# StepperDriver_Rev1.net
KiCad netlist of a schematic drawn in EAGLE
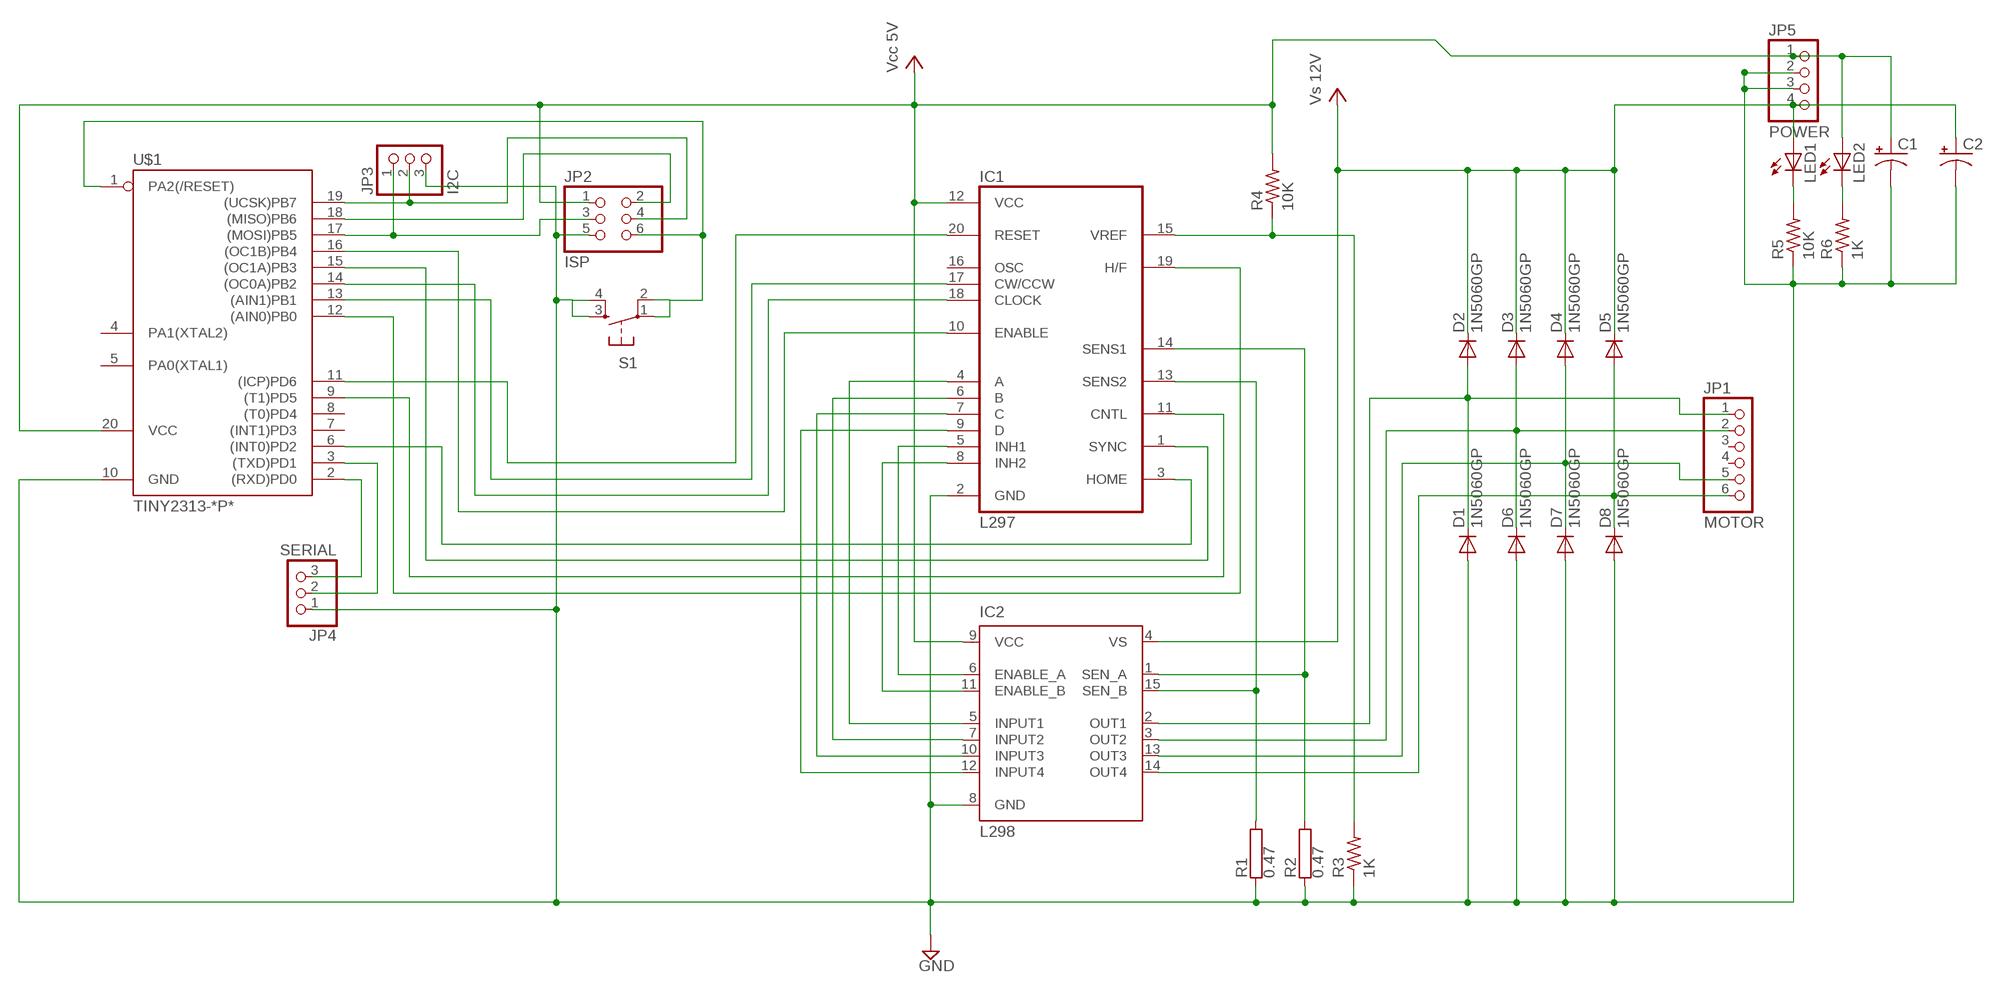
[diagram p0: schematic, sheet 1]

(export (version "E")
  (design (tool "Eeschema 10.0.6"))
  (components
    (comp (ref "C1")
      (value "CPOL-USE2.5-6")
      (footprint "eagle-import:E2,5-6")
      (libsource (lib "eagle-import") (part "CPOL-USE2.5-6"))
    )
    (comp (ref "C2")
      (value "CPOL-USE2.5-6")
      (footprint "eagle-import:E2,5-6")
      (libsource (lib "eagle-import") (part "CPOL-USE2.5-6"))
    )
    (comp (ref "D1")
      (value "1N5060GP")
      (footprint "eagle-import:DO15-12")
      (libsource (lib "eagle-import") (part "1N5060GP"))
    )
    (comp (ref "D2")
      (value "1N5060GP")
      (footprint "eagle-import:DO15-12")
      (libsource (lib "eagle-import") (part "1N5060GP"))
    )
    (comp (ref "D3")
      (value "1N5060GP")
      (footprint "eagle-import:DO15-12")
      (libsource (lib "eagle-import") (part "1N5060GP"))
    )
    (comp (ref "D4")
      (value "1N5060GP")
      (footprint "eagle-import:DO15-12")
      (libsource (lib "eagle-import") (part "1N5060GP"))
    )
    (comp (ref "D5")
      (value "1N5060GP")
      (footprint "eagle-import:DO15-12")
      (libsource (lib "eagle-import") (part "1N5060GP"))
    )
    (comp (ref "D6")
      (value "1N5060GP")
      (footprint "eagle-import:DO15-12")
      (libsource (lib "eagle-import") (part "1N5060GP"))
    )
    (comp (ref "D7")
      (value "1N5060GP")
      (footprint "eagle-import:DO15-12")
      (libsource (lib "eagle-import") (part "1N5060GP"))
    )
    (comp (ref "D8")
      (value "1N5060GP")
      (footprint "eagle-import:DO15-12")
      (libsource (lib "eagle-import") (part "1N5060GP"))
    )
    (comp (ref "IC1")
      (value "L297")
      (footprint "eagle-import:DIL20")
      (fields (field (name "MPN") "L297/1"))
      (libsource (lib "eagle-import") (part "L297"))
    )
    (comp (ref "IC2")
      (value "L298")
      (footprint "eagle-import:MULTIWATT-15")
      (fields (field (name "MPN") "L298N"))
      (libsource (lib "eagle-import") (part "L298"))
    )
    (comp (ref "JP1")
      (value "MOTOR")
      (footprint "eagle-import:1X06")
      (libsource (lib "eagle-import") (part "PINHD-1X6"))
    )
    (comp (ref "JP2")
      (value "ISP")
      (footprint "eagle-import:2X03")
      (libsource (lib "eagle-import") (part "PINHD-2X3"))
    )
    (comp (ref "JP3")
      (value "I2C")
      (footprint "eagle-import:1X03")
      (libsource (lib "eagle-import") (part "PINHD-1X3"))
    )
    (comp (ref "JP4")
      (value "SERIAL")
      (footprint "eagle-import:1X03")
      (libsource (lib "eagle-import") (part "PINHD-1X3"))
    )
    (comp (ref "JP5")
      (value "POWER")
      (footprint "eagle-import:1X04")
      (libsource (lib "eagle-import") (part "PINHD-1X4"))
    )
    (comp (ref "LED1")
      (value "LED5MM")
      (footprint "eagle-import:LED5MM")
      (libsource (lib "eagle-import") (part "LED5MM"))
    )
    (comp (ref "LED2")
      (value "LED5MM")
      (footprint "eagle-import:LED5MM")
      (libsource (lib "eagle-import") (part "LED5MM"))
    )
    (comp (ref "R1")
      (value "0.47")
      (footprint "eagle-import:HPS932")
      (libsource (lib "eagle-import") (part "RHPS932"))
    )
    (comp (ref "R2")
      (value "0.47")
      (footprint "eagle-import:HPS932")
      (libsource (lib "eagle-import") (part "RHPS932"))
    )
    (comp (ref "R3")
      (value "1K")
      (footprint "eagle-import:0204_7")
      (libsource (lib "eagle-import") (part "R-US_0204/7"))
    )
    (comp (ref "R4")
      (value "10K")
      (footprint "eagle-import:0204_7")
      (libsource (lib "eagle-import") (part "R-US_0204/7"))
    )
    (comp (ref "R5")
      (value "10K")
      (footprint "eagle-import:0207_7")
      (libsource (lib "eagle-import") (part "R-US_0207/7"))
    )
    (comp (ref "R6")
      (value "1K")
      (footprint "eagle-import:0207_7")
      (libsource (lib "eagle-import") (part "R-US_0207/7"))
    )
    (comp (ref "S1")
      (value "TAC_SWITCHPTH")
      (footprint "eagle-import:TACTILE-PTH")
      (libsource (lib "eagle-import") (part "TAC_SWITCHPTH"))
    )
    (comp (ref "U$1")
      (value "TINY2313-*P*")
      (footprint "eagle-import:DIL20")
      (libsource (lib "eagle-import") (part "TINY2313-P"))
    )
  )
  (nets
    (net (code "1") (name "GND") (class "Default")
      (node (ref "C1") (pin "-") (pinfunction "-_-") (pintype "passive"))
      (node (ref "C2") (pin "-") (pinfunction "-_-") (pintype "passive"))
      (node (ref "D1") (pin "A") (pinfunction "A_A") (pintype "passive"))
      (node (ref "D6") (pin "A") (pinfunction "A_A") (pintype "passive"))
      (node (ref "D7") (pin "A") (pinfunction "A_A") (pintype "passive"))
      (node (ref "D8") (pin "A") (pinfunction "A_A") (pintype "passive"))
      (node (ref "IC1") (pin "2") (pinfunction "GND_2") (pintype "power_in"))
      (node (ref "IC2") (pin "8") (pinfunction "GND_8") (pintype "power_in"))
      (node (ref "JP2") (pin "5") (pinfunction "5_5") (pintype "passive"))
      (node (ref "JP3") (pin "3") (pinfunction "3_3") (pintype "passive"))
      (node (ref "JP4") (pin "1") (pinfunction "1_1") (pintype "passive"))
      (node (ref "JP5") (pin "2") (pinfunction "2_2") (pintype "passive"))
      (node (ref "JP5") (pin "3") (pinfunction "3_3") (pintype "passive"))
      (node (ref "R1") (pin "1") (pinfunction "1_1") (pintype "passive"))
      (node (ref "R2") (pin "1") (pinfunction "1_1") (pintype "passive"))
      (node (ref "R3") (pin "1") (pinfunction "1_1") (pintype "passive"))
      (node (ref "R5") (pin "1") (pinfunction "1_1") (pintype "passive"))
      (node (ref "R6") (pin "1") (pinfunction "1_1") (pintype "passive"))
      (node (ref "S1") (pin "3") (pinfunction "3_3") (pintype "passive"))
      (node (ref "S1") (pin "4") (pinfunction "4_4") (pintype "passive"))
      (node (ref "U$1") (pin "10") (pinfunction "GND_10") (pintype "power_in"))
    )
    (net (code "2") (name "Net-(IC1-A)") (class "Default")
      (node (ref "IC1") (pin "4") (pinfunction "A_4") (pintype "output"))
      (node (ref "IC2") (pin "5") (pinfunction "INPUT1_5") (pintype "input"))
    )
    (net (code "3") (name "Net-(IC1-B)") (class "Default")
      (node (ref "IC1") (pin "6") (pinfunction "B_6") (pintype "output"))
      (node (ref "IC2") (pin "7") (pinfunction "INPUT2_7") (pintype "input"))
    )
    (net (code "4") (name "Net-(IC1-C)") (class "Default")
      (node (ref "IC1") (pin "7") (pinfunction "C_7") (pintype "output"))
      (node (ref "IC2") (pin "10") (pinfunction "INPUT3_10") (pintype "input"))
    )
    (net (code "5") (name "Net-(IC1-CLOCK)") (class "Default")
      (node (ref "IC1") (pin "18") (pinfunction "CLOCK_18") (pintype "input"))
      (node (ref "U$1") (pin "14") (pinfunction "(OC0A)PB2_14") (pintype "bidirectional"))
    )
    (net (code "6") (name "Net-(IC1-CNTL)") (class "Default")
      (node (ref "IC1") (pin "11") (pinfunction "CNTL_11") (pintype "input"))
      (node (ref "U$1") (pin "9") (pinfunction "(T1)PD5_9") (pintype "bidirectional"))
    )
    (net (code "7") (name "Net-(IC1-CW{slash}CCW)") (class "Default")
      (node (ref "IC1") (pin "17") (pinfunction "CW/CCW_17") (pintype "input"))
      (node (ref "U$1") (pin "13") (pinfunction "(AIN1)PB1_13") (pintype "bidirectional"))
    )
    (net (code "8") (name "Net-(IC1-D)") (class "Default")
      (node (ref "IC1") (pin "9") (pinfunction "D_9") (pintype "output"))
      (node (ref "IC2") (pin "12") (pinfunction "INPUT4_12") (pintype "input"))
    )
    (net (code "9") (name "Net-(IC1-ENABLE)") (class "Default")
      (node (ref "IC1") (pin "10") (pinfunction "ENABLE_10") (pintype "input"))
      (node (ref "U$1") (pin "16") (pinfunction "(OC1B)PB4_16") (pintype "bidirectional"))
    )
    (net (code "10") (name "Net-(IC1-HOME)") (class "Default")
      (node (ref "IC1") (pin "3") (pinfunction "HOME_3") (pintype "output"))
      (node (ref "U$1") (pin "6") (pinfunction "(INT0)PD2_6") (pintype "bidirectional"))
    )
    (net (code "11") (name "Net-(IC1-H{slash}F)") (class "Default")
      (node (ref "IC1") (pin "19") (pinfunction "H/F_19") (pintype "input"))
      (node (ref "U$1") (pin "12") (pinfunction "(AIN0)PB0_12") (pintype "bidirectional"))
    )
    (net (code "12") (name "Net-(IC1-INH1)") (class "Default")
      (node (ref "IC1") (pin "5") (pinfunction "INH1_5") (pintype "output"))
      (node (ref "IC2") (pin "6") (pinfunction "ENABLE_A_6") (pintype "input"))
    )
    (net (code "13") (name "Net-(IC1-INH2)") (class "Default")
      (node (ref "IC1") (pin "8") (pinfunction "INH2_8") (pintype "output"))
      (node (ref "IC2") (pin "11") (pinfunction "ENABLE_B_11") (pintype "input"))
    )
    (net (code "14") (name "Net-(IC1-RESET)") (class "Default")
      (node (ref "IC1") (pin "20") (pinfunction "RESET_20") (pintype "input"))
      (node (ref "U$1") (pin "11") (pinfunction "(ICP)PD6_11") (pintype "bidirectional"))
    )
    (net (code "15") (name "Net-(IC1-SENS1)") (class "Default")
      (node (ref "IC1") (pin "14") (pinfunction "SENS1_14") (pintype "output"))
      (node (ref "IC2") (pin "1") (pinfunction "SEN_A_1") (pintype "input"))
      (node (ref "R2") (pin "2") (pinfunction "2_2") (pintype "passive"))
    )
    (net (code "16") (name "Net-(IC1-SENS2)") (class "Default")
      (node (ref "IC1") (pin "13") (pinfunction "SENS2_13") (pintype "output"))
      (node (ref "IC2") (pin "15") (pinfunction "SEN_B_15") (pintype "input"))
      (node (ref "R1") (pin "2") (pinfunction "2_2") (pintype "passive"))
    )
    (net (code "17") (name "Net-(IC1-SYNC)") (class "Default")
      (node (ref "IC1") (pin "1") (pinfunction "SYNC_1") (pintype "output"))
      (node (ref "U$1") (pin "15") (pinfunction "(OC1A)PB3_15") (pintype "bidirectional"))
    )
    (net (code "18") (name "Net-(IC1-VREF)") (class "Default")
      (node (ref "IC1") (pin "15") (pinfunction "VREF_15") (pintype "input"))
      (node (ref "R3") (pin "2") (pinfunction "2_2") (pintype "passive"))
      (node (ref "R4") (pin "1") (pinfunction "1_1") (pintype "passive"))
    )
    (net (code "19") (name "Net-(IC2-OUT1)") (class "Default")
      (node (ref "D1") (pin "C") (pinfunction "C_C") (pintype "passive"))
      (node (ref "D2") (pin "A") (pinfunction "A_A") (pintype "passive"))
      (node (ref "IC2") (pin "2") (pinfunction "OUT1_2") (pintype "output"))
      (node (ref "JP1") (pin "1") (pinfunction "1_1") (pintype "passive"))
    )
    (net (code "20") (name "Net-(IC2-OUT2)") (class "Default")
      (node (ref "D3") (pin "A") (pinfunction "A_A") (pintype "passive"))
      (node (ref "D6") (pin "C") (pinfunction "C_C") (pintype "passive"))
      (node (ref "IC2") (pin "3") (pinfunction "OUT2_3") (pintype "output"))
      (node (ref "JP1") (pin "2") (pinfunction "2_2") (pintype "passive"))
    )
    (net (code "21") (name "Net-(IC2-OUT3)") (class "Default")
      (node (ref "D4") (pin "A") (pinfunction "A_A") (pintype "passive"))
      (node (ref "D7") (pin "C") (pinfunction "C_C") (pintype "passive"))
      (node (ref "IC2") (pin "13") (pinfunction "OUT3_13") (pintype "output"))
      (node (ref "JP1") (pin "5") (pinfunction "5_5") (pintype "passive"))
    )
    (net (code "22") (name "Net-(IC2-OUT4)") (class "Default")
      (node (ref "D5") (pin "A") (pinfunction "A_A") (pintype "passive"))
      (node (ref "D8") (pin "C") (pinfunction "C_C") (pintype "passive"))
      (node (ref "IC2") (pin "14") (pinfunction "OUT4_14") (pintype "output"))
      (node (ref "JP1") (pin "6") (pinfunction "6_6") (pintype "passive"))
    )
    (net (code "23") (name "Net-(LED1-C)") (class "Default")
      (node (ref "LED1") (pin "K") (pinfunction "C_K") (pintype "passive"))
      (node (ref "R5") (pin "2") (pinfunction "2_2") (pintype "passive"))
    )
    (net (code "24") (name "Net-(LED2-C)") (class "Default")
      (node (ref "LED2") (pin "K") (pinfunction "C_K") (pintype "passive"))
      (node (ref "R6") (pin "2") (pinfunction "2_2") (pintype "passive"))
    )
    (net (code "25") (name "Net-(U$1-(MISO)PB6)") (class "Default")
      (node (ref "JP2") (pin "2") (pinfunction "2_2") (pintype "passive"))
      (node (ref "U$1") (pin "18") (pinfunction "(MISO)PB6_18") (pintype "bidirectional"))
    )
    (net (code "26") (name "Net-(U$1-(MOSI)PB5)") (class "Default")
      (node (ref "JP2") (pin "3") (pinfunction "3_3") (pintype "passive"))
      (node (ref "JP3") (pin "1") (pinfunction "1_1") (pintype "passive"))
      (node (ref "U$1") (pin "17") (pinfunction "(MOSI)PB5_17") (pintype "bidirectional"))
    )
    (net (code "27") (name "Net-(U$1-(RXD)PD0)") (class "Default")
      (node (ref "JP4") (pin "3") (pinfunction "3_3") (pintype "passive"))
      (node (ref "U$1") (pin "2") (pinfunction "(RXD)PD0_2") (pintype "bidirectional"))
    )
    (net (code "28") (name "Net-(U$1-(TXD)PD1)") (class "Default")
      (node (ref "JP4") (pin "2") (pinfunction "2_2") (pintype "passive"))
      (node (ref "U$1") (pin "3") (pinfunction "(TXD)PD1_3") (pintype "bidirectional"))
    )
    (net (code "29") (name "Net-(U$1-(UCSK)PB7)") (class "Default")
      (node (ref "JP2") (pin "4") (pinfunction "4_4") (pintype "passive"))
      (node (ref "JP3") (pin "2") (pinfunction "2_2") (pintype "passive"))
      (node (ref "U$1") (pin "19") (pinfunction "(UCSK)PB7_19") (pintype "bidirectional"))
    )
    (net (code "30") (name "Net-(U$1-PA2({slash}RESET))") (class "Default")
      (node (ref "JP2") (pin "6") (pinfunction "6_6") (pintype "passive"))
      (node (ref "S1") (pin "1") (pinfunction "1_1") (pintype "passive"))
      (node (ref "S1") (pin "2") (pinfunction "2_2") (pintype "passive"))
      (node (ref "U$1") (pin "1") (pinfunction "PA2(/RESET)_1") (pintype "input"))
    )
    (net (code "31") (name "Vcc 5V") (class "Default")
      (node (ref "C1") (pin "+") (pinfunction "+_+") (pintype "passive"))
      (node (ref "IC1") (pin "12") (pinfunction "VCC_12") (pintype "power_in"))
      (node (ref "IC2") (pin "9") (pinfunction "VCC_9") (pintype "power_in"))
      (node (ref "JP2") (pin "1") (pinfunction "1_1") (pintype "passive"))
      (node (ref "JP5") (pin "1") (pinfunction "1_1") (pintype "passive"))
      (node (ref "LED2") (pin "A") (pinfunction "A_A") (pintype "passive"))
      (node (ref "R4") (pin "2") (pinfunction "2_2") (pintype "passive"))
      (node (ref "U$1") (pin "20") (pinfunction "VCC_20") (pintype "power_in"))
    )
    (net (code "32") (name "Vs 12V") (class "Default")
      (node (ref "C2") (pin "+") (pinfunction "+_+") (pintype "passive"))
      (node (ref "D2") (pin "C") (pinfunction "C_C") (pintype "passive"))
      (node (ref "D3") (pin "C") (pinfunction "C_C") (pintype "passive"))
      (node (ref "D4") (pin "C") (pinfunction "C_C") (pintype "passive"))
      (node (ref "D5") (pin "C") (pinfunction "C_C") (pintype "passive"))
      (node (ref "IC2") (pin "4") (pinfunction "VS_4") (pintype "power_in"))
      (node (ref "JP5") (pin "4") (pinfunction "4_4") (pintype "passive"))
      (node (ref "LED1") (pin "A") (pinfunction "A_A") (pintype "passive"))
    )
    (net (code "33") (name "unconnected-(IC1-OSC-Pad16)") (class "Default")
      (node (ref "IC1") (pin "16") (pinfunction "OSC_16") (pintype "bidirectional"))
    )
    (net (code "34") (name "unconnected-(JP1-Pad3)") (class "Default")
      (node (ref "JP1") (pin "3") (pinfunction "3_3") (pintype "passive"))
    )
    (net (code "35") (name "unconnected-(JP1-Pad4)") (class "Default")
      (node (ref "JP1") (pin "4") (pinfunction "4_4") (pintype "passive"))
    )
    (net (code "36") (name "unconnected-(U$1-(INT1)PD3-Pad7)") (class "Default")
      (node (ref "U$1") (pin "7") (pinfunction "(INT1)PD3_7") (pintype "bidirectional"))
    )
    (net (code "37") (name "unconnected-(U$1-(T0)PD4-Pad8)") (class "Default")
      (node (ref "U$1") (pin "8") (pinfunction "(T0)PD4_8") (pintype "bidirectional"))
    )
    (net (code "38") (name "unconnected-(U$1-PA0(XTAL1)-Pad5)") (class "Default")
      (node (ref "U$1") (pin "5") (pinfunction "PA0(XTAL1)_5") (pintype "bidirectional"))
    )
    (net (code "39") (name "unconnected-(U$1-PA1(XTAL2)-Pad4)") (class "Default")
      (node (ref "U$1") (pin "4") (pinfunction "PA1(XTAL2)_4") (pintype "bidirectional"))
    )
  )
)
